# 06-SIM800C.net
KiCad netlist of a schematic drawn in Altium Designer
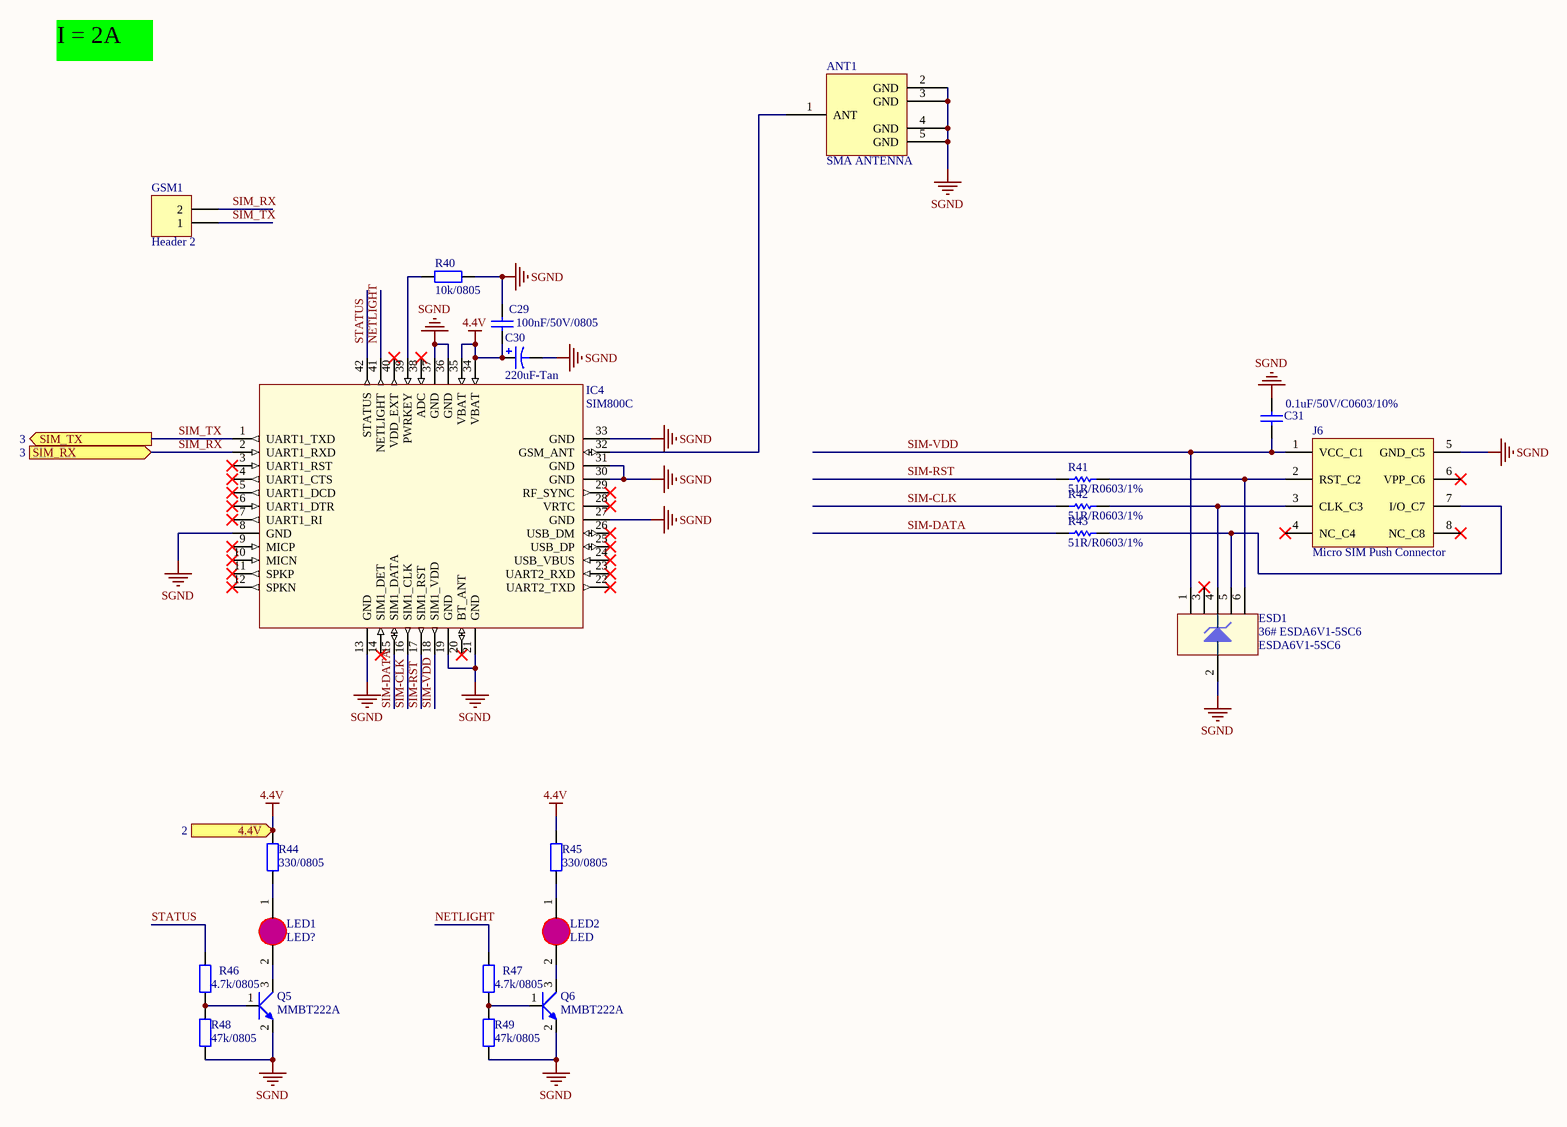
[diagram p0: 06-SIM800C.SchDoc]

(export (version "E")
  (design (tool "Eeschema 10.0.6"))
  (components
    (comp (ref "ANT1")
      (value "SMA ANTENNA")
      (footprint "atenna_ra")
      (libsource (lib "Air_System_lib") (part "SMA ANTENNA"))
    )
    (comp (ref "C29")
      (value "100nF/50V/0805")
      (footprint "Cap Ceramic 0805 SMD")
      (fields (field (name "PUBLISHER") "Altium Limited"))
      (libsource (lib "NBBLib 14-03-2012") (part "CapSMD"))
    )
    (comp (ref "C30")
      (value "220uF-Tan")
      (footprint "CAP TANT CASE E SMD")
      (libsource (lib "Air_System_lib") (part "CAP1210-Tan"))
    )
    (comp (ref "C31")
      (value "0.1uF/50V/C0603/10%")
      (footprint "Cap Ceramic 0603 SMD")
      (description "CAP CER 0.1UF 50V 10% X7R 0603")
      (fields
        (field (name "MANUFACTURER") "Murata Electronics North America")
        (field (name "MANUFACTURER PART NUMBER") "GRM188R71H104KA93D")
      )
      (libsource (lib "GSHT_181013") (part "0.1uF/50V/C0603/10%"))
    )
    (comp (ref "ESD1")
      (value "36# ESDA6V1-5SC6")
      (footprint "36# ESDA6V1-5SC6")
      (description "TRANSIL™ ARRAY FOR ESD PROTECTION")
      (fields (field (name "SUPPLIER PART NUMBER 1") "ESDA6V1-5SC6"))
      (libsource (lib "GSHT_181013") (part "36# ESDA6V1-5SC6"))
    )
    (comp (ref "GSM1")
      (value "Header 2")
      (footprint "Header_2")
      (description "Header, 2-Pin")
      (fields (field (name "PUBLISHER") "Altium Limited"))
      (libsource (lib "NBBLib 14-03-2012") (part "Header 2"))
    )
    (comp (ref "IC4")
      (value "SIM800C")
      (footprint "SIM800C")
      (description "SIM800C V1.00")
      (libsource (lib "LIEMTHANH_LIB") (part "SIM800C"))
    )
    (comp (ref "J6")
      (value "Micro SIM Push Connector")
      (footprint "9# SIM holder")
      (libsource (lib "GSHT_181013") (part "9#SIM Card Holder KF-016"))
    )
    (comp (ref "LED1")
      (value "LED?")
      (footprint "Led 0805R")
      (description "LED SMD 0805")
      (libsource (lib "NBBLib 14-03-2012") (part "LED0805"))
    )
    (comp (ref "LED2")
      (value "LED")
      (footprint "Led 0805R")
      (description "LED SMD 0805")
      (libsource (lib "NBBLib 14-03-2012") (part "LED0805"))
    )
    (comp (ref "Q5")
      (value "MMBT222A")
      (footprint "MMBT2222A")
      (libsource (lib "Air_System_lib") (part "MMBT222A"))
    )
    (comp (ref "Q6")
      (value "MMBT222A")
      (footprint "MMBT2222A")
      (libsource (lib "Air_System_lib") (part "MMBT222A"))
    )
    (comp (ref "R40")
      (value "10k/0805")
      (footprint "RESC2012(0805)")
      (description "Resistor SMD 0805")
      (fields (field (name "PUBLISHER") "Altium Limited"))
      (libsource (lib "") (part "R0805_1"))
    )
    (comp (ref "R41")
      (value "51R/R0603/1%")
      (footprint "Res 0603 SMD")
      (description "RES SMD 22 OHM 1% 1/10W 0603")
      (fields
        (field (name "MANUFACTURER") "Yageo")
        (field (name "MANUFACTURER PART NUMBER") "RC0603FR-0722RL")
      )
      (libsource (lib "GSHT_181013") (part "22R/R0603/1%"))
    )
    (comp (ref "R42")
      (value "51R/R0603/1%")
      (footprint "Res 0603 SMD")
      (description "RES SMD 22 OHM 1% 1/10W 0603")
      (fields
        (field (name "MANUFACTURER") "Yageo")
        (field (name "MANUFACTURER PART NUMBER") "RC0603FR-0722RL")
      )
      (libsource (lib "GSHT_181013") (part "22R/R0603/1%"))
    )
    (comp (ref "R43")
      (value "51R/R0603/1%")
      (footprint "Res 0603 SMD")
      (description "RES SMD 22 OHM 1% 1/10W 0603")
      (fields
        (field (name "MANUFACTURER") "Yageo")
        (field (name "MANUFACTURER PART NUMBER") "RC0603FR-0722RL")
      )
      (libsource (lib "GSHT_181013") (part "22R/R0603/1%"))
    )
    (comp (ref "R44")
      (value "330/0805")
      (footprint "RESC2012(0805)")
      (description "Resistor SMD 0805")
      (fields (field (name "Comment") "R0805") (field (name "PUBLISHER") "Altium Limited"))
      (libsource (lib "NBBLib 14-03-2012") (part "R0805"))
    )
    (comp (ref "R45")
      (value "330/0805")
      (footprint "RESC2012(0805)")
      (description "Resistor SMD 0805")
      (fields (field (name "Comment") "R0805") (field (name "PUBLISHER") "Altium Limited"))
      (libsource (lib "NBBLib 14-03-2012") (part "R0805"))
    )
    (comp (ref "R46")
      (value "4.7k/0805")
      (footprint "RESC2012(0805)")
      (description "Resistor SMD 0805")
      (fields (field (name "Comment") "R0805") (field (name "PUBLISHER") "Altium Limited"))
      (libsource (lib "NBBLib 14-03-2012") (part "R0805"))
    )
    (comp (ref "R47")
      (value "4.7k/0805")
      (footprint "RESC2012(0805)")
      (description "Resistor SMD 0805")
      (fields (field (name "Comment") "R0805") (field (name "PUBLISHER") "Altium Limited"))
      (libsource (lib "NBBLib 14-03-2012") (part "R0805"))
    )
    (comp (ref "R48")
      (value "47k/0805")
      (footprint "RESC2012(0805)")
      (description "Resistor SMD 0805")
      (fields (field (name "Comment") "R0805") (field (name "PUBLISHER") "Altium Limited"))
      (libsource (lib "NBBLib 14-03-2012") (part "R0805"))
    )
    (comp (ref "R49")
      (value "47k/0805")
      (footprint "RESC2012(0805)")
      (description "Resistor SMD 0805")
      (fields (field (name "Comment") "R0805") (field (name "PUBLISHER") "Altium Limited"))
      (libsource (lib "NBBLib 14-03-2012") (part "R0805"))
    )
  )
  (nets
    (net (code "2") (name "/NETLIGHT") (class "Default")
      (node (ref "IC4") (pin "41") (pinfunction "NETLIGHT_41") (pintype "output"))
      (node (ref "R47") (pin "1") (pinfunction "1_1") (pintype "passive"))
    )
    (net (code "3") (name "/SIM-CLK") (class "Default")
      (node (ref "IC4") (pin "16") (pinfunction "SIM1_CLK_16") (pintype "output"))
      (node (ref "R42") (pin "1") (pinfunction "1_1") (pintype "passive"))
    )
    (net (code "4") (name "/SIM-DATA") (class "Default")
      (node (ref "IC4") (pin "15") (pinfunction "SIM1_DATA_15") (pintype "bidirectional"))
      (node (ref "R43") (pin "1") (pinfunction "1_1") (pintype "passive"))
    )
    (net (code "5") (name "/SIM-RST") (class "Default")
      (node (ref "IC4") (pin "17") (pinfunction "SIM1_RST_17") (pintype "output"))
      (node (ref "R41") (pin "1") (pinfunction "1_1") (pintype "passive"))
    )
    (net (code "6") (name "/SIM-VDD") (class "Default")
      (node (ref "C31") (pin "1") (pinfunction "1_1") (pintype "passive"))
      (node (ref "ESD1") (pin "1") (pinfunction "IO1_1") (pintype "passive"))
      (node (ref "IC4") (pin "18") (pinfunction "SIM1_VDD_18") (pintype "output"))
      (node (ref "J6") (pin "1") (pinfunction "VCC_C1_1") (pintype "passive"))
    )
    (net (code "7") (name "/SIM_RX") (class "Default")
      (node (ref "GSM1") (pin "2") (pinfunction "2_2") (pintype "passive"))
      (node (ref "IC4") (pin "2") (pinfunction "UART1_RXD_2") (pintype "input"))
    )
    (net (code "8") (name "/SIM_TX") (class "Default")
      (node (ref "GSM1") (pin "1") (pinfunction "1_1") (pintype "passive"))
      (node (ref "IC4") (pin "1") (pinfunction "UART1_TXD_1") (pintype "output"))
    )
    (net (code "9") (name "/STATUS") (class "Default")
      (node (ref "IC4") (pin "42") (pinfunction "STATUS_42") (pintype "output"))
      (node (ref "R46") (pin "1") (pinfunction "1_1") (pintype "passive"))
    )
    (net (code "10") (name "4.4V") (class "Default")
      (node (ref "C29") (pin "1") (pinfunction "1_1") (pintype "passive"))
      (node (ref "C30") (pin "1") (pinfunction "1_1") (pintype "passive"))
      (node (ref "IC4") (pin "34") (pinfunction "VBAT_34") (pintype "input"))
      (node (ref "IC4") (pin "35") (pinfunction "VBAT_35") (pintype "input"))
      (node (ref "R44") (pin "1") (pinfunction "1_1") (pintype "passive"))
      (node (ref "R45") (pin "1") (pinfunction "1_1") (pintype "passive"))
    )
    (net (code "11") (name "Net-(ANT1-ANT)") (class "Default")
      (node (ref "ANT1") (pin "1") (pinfunction "ANT_1") (pintype "passive"))
      (node (ref "IC4") (pin "32") (pinfunction "GSM_ANT_32") (pintype "bidirectional"))
    )
    (net (code "12") (name "Net-(ESD1-IO3)") (class "Default")
      (node (ref "ESD1") (pin "4") (pinfunction "IO3_4") (pintype "passive"))
      (node (ref "J6") (pin "3") (pinfunction "CLK_C3_3") (pintype "passive"))
      (node (ref "R42") (pin "2") (pinfunction "2_2") (pintype "passive"))
    )
    (net (code "13") (name "Net-(ESD1-IO4)") (class "Default")
      (node (ref "ESD1") (pin "5") (pinfunction "IO4_5") (pintype "passive"))
      (node (ref "J6") (pin "7") (pinfunction "I/O_C7_7") (pintype "passive"))
      (node (ref "R43") (pin "2") (pinfunction "2_2") (pintype "passive"))
    )
    (net (code "14") (name "Net-(ESD1-IO5)") (class "Default")
      (node (ref "ESD1") (pin "6") (pinfunction "IO5_6") (pintype "passive"))
      (node (ref "J6") (pin "2") (pinfunction "RST_C2_2") (pintype "passive"))
      (node (ref "R41") (pin "2") (pinfunction "2_2") (pintype "passive"))
    )
    (net (code "15") (name "Net-(IC4-PWRKEY)") (class "Default")
      (node (ref "IC4") (pin "39") (pinfunction "PWRKEY_39") (pintype "input"))
      (node (ref "R40") (pin "1") (pinfunction "1_1") (pintype "passive"))
    )
    (net (code "16") (name "Net-(LED1-A)") (class "Default")
      (node (ref "LED1") (pin "1") (pinfunction "A_1") (pintype "passive"))
      (node (ref "R44") (pin "2") (pinfunction "2_2") (pintype "passive"))
    )
    (net (code "17") (name "Net-(LED1-K)") (class "Default")
      (node (ref "LED1") (pin "2") (pinfunction "K_2") (pintype "passive"))
      (node (ref "Q5") (pin "3") (pinfunction "3_3") (pintype "passive"))
    )
    (net (code "18") (name "Net-(LED2-A)") (class "Default")
      (node (ref "LED2") (pin "1") (pinfunction "A_1") (pintype "passive"))
      (node (ref "R45") (pin "2") (pinfunction "2_2") (pintype "passive"))
    )
    (net (code "19") (name "Net-(LED2-K)") (class "Default")
      (node (ref "LED2") (pin "2") (pinfunction "K_2") (pintype "passive"))
      (node (ref "Q6") (pin "3") (pinfunction "3_3") (pintype "passive"))
    )
    (net (code "20") (name "Net-(Q5-Pad1)") (class "Default")
      (node (ref "Q5") (pin "1") (pinfunction "1_1") (pintype "passive"))
      (node (ref "R46") (pin "2") (pinfunction "2_2") (pintype "passive"))
      (node (ref "R48") (pin "1") (pinfunction "1_1") (pintype "passive"))
    )
    (net (code "21") (name "Net-(Q6-Pad1)") (class "Default")
      (node (ref "Q6") (pin "1") (pinfunction "1_1") (pintype "passive"))
      (node (ref "R47") (pin "2") (pinfunction "2_2") (pintype "passive"))
      (node (ref "R49") (pin "1") (pinfunction "1_1") (pintype "passive"))
    )
    (net (code "22") (name "SGND") (class "Default")
      (node (ref "ANT1") (pin "2") (pinfunction "GND_2") (pintype "passive"))
      (node (ref "ANT1") (pin "3") (pinfunction "GND_3") (pintype "passive"))
      (node (ref "ANT1") (pin "4") (pinfunction "GND_4") (pintype "passive"))
      (node (ref "ANT1") (pin "5") (pinfunction "GND_5") (pintype "passive"))
      (node (ref "C29") (pin "2") (pinfunction "2_2") (pintype "passive"))
      (node (ref "C30") (pin "2") (pinfunction "2_2") (pintype "passive"))
      (node (ref "C31") (pin "2") (pinfunction "2_2") (pintype "passive"))
      (node (ref "ESD1") (pin "2") (pinfunction "GND_2") (pintype "passive"))
      (node (ref "IC4") (pin "13") (pinfunction "GND_13") (pintype "power_in"))
      (node (ref "IC4") (pin "19") (pinfunction "GND_19") (pintype "power_in"))
      (node (ref "IC4") (pin "21") (pinfunction "GND_21") (pintype "power_in"))
      (node (ref "IC4") (pin "27") (pinfunction "GND_27") (pintype "power_in"))
      (node (ref "IC4") (pin "30") (pinfunction "GND_30") (pintype "power_in"))
      (node (ref "IC4") (pin "31") (pinfunction "GND_31") (pintype "power_in"))
      (node (ref "IC4") (pin "33") (pinfunction "GND_33") (pintype "power_in"))
      (node (ref "IC4") (pin "36") (pinfunction "GND_36") (pintype "power_in"))
      (node (ref "IC4") (pin "37") (pinfunction "GND_37") (pintype "power_in"))
      (node (ref "IC4") (pin "8") (pinfunction "GND_8") (pintype "power_in"))
      (node (ref "J6") (pin "5") (pinfunction "GND_C5_5") (pintype "passive"))
      (node (ref "Q5") (pin "2") (pinfunction "2_2") (pintype "passive"))
      (node (ref "Q6") (pin "2") (pinfunction "2_2") (pintype "passive"))
      (node (ref "R40") (pin "2") (pinfunction "2_2") (pintype "passive"))
      (node (ref "R48") (pin "2") (pinfunction "2_2") (pintype "passive"))
      (node (ref "R49") (pin "2") (pinfunction "2_2") (pintype "passive"))
    )
    (net (code "23") (name "unconnected-(ESD1-IO2-Pad3)") (class "Default")
      (node (ref "ESD1") (pin "3") (pinfunction "IO2_3") (pintype "passive+no_connect"))
    )
    (net (code "24") (name "unconnected-(IC4-ADC-Pad38)") (class "Default")
      (node (ref "IC4") (pin "38") (pinfunction "ADC_38") (pintype "input+no_connect"))
    )
    (net (code "25") (name "unconnected-(IC4-BT_ANT-Pad20)") (class "Default")
      (node (ref "IC4") (pin "20") (pinfunction "BT_ANT_20") (pintype "bidirectional+no_connect"))
    )
    (net (code "26") (name "unconnected-(IC4-MICN-Pad10)") (class "Default")
      (node (ref "IC4") (pin "10") (pinfunction "MICN_10") (pintype "input+no_connect"))
    )
    (net (code "27") (name "unconnected-(IC4-MICP-Pad9)") (class "Default")
      (node (ref "IC4") (pin "9") (pinfunction "MICP_9") (pintype "input+no_connect"))
    )
    (net (code "28") (name "unconnected-(IC4-RF_SYNC-Pad29)") (class "Default")
      (node (ref "IC4") (pin "29") (pinfunction "RF_SYNC_29") (pintype "output+no_connect"))
    )
    (net (code "29") (name "unconnected-(IC4-SIM1_DET-Pad14)") (class "Default")
      (node (ref "IC4") (pin "14") (pinfunction "SIM1_DET_14") (pintype "input+no_connect"))
    )
    (net (code "30") (name "unconnected-(IC4-SPKN-Pad12)") (class "Default")
      (node (ref "IC4") (pin "12") (pinfunction "SPKN_12") (pintype "output+no_connect"))
    )
    (net (code "31") (name "unconnected-(IC4-SPKP-Pad11)") (class "Default")
      (node (ref "IC4") (pin "11") (pinfunction "SPKP_11") (pintype "output+no_connect"))
    )
    (net (code "32") (name "unconnected-(IC4-UART1_CTS-Pad4)") (class "Default")
      (node (ref "IC4") (pin "4") (pinfunction "UART1_CTS_4") (pintype "output+no_connect"))
    )
    (net (code "33") (name "unconnected-(IC4-UART1_DCD-Pad5)") (class "Default")
      (node (ref "IC4") (pin "5") (pinfunction "UART1_DCD_5") (pintype "output+no_connect"))
    )
    (net (code "34") (name "unconnected-(IC4-UART1_DTR-Pad6)") (class "Default")
      (node (ref "IC4") (pin "6") (pinfunction "UART1_DTR_6") (pintype "input+no_connect"))
    )
    (net (code "35") (name "unconnected-(IC4-UART1_RI-Pad7)") (class "Default")
      (node (ref "IC4") (pin "7") (pinfunction "UART1_RI_7") (pintype "output+no_connect"))
    )
    (net (code "36") (name "unconnected-(IC4-UART1_RST-Pad3)") (class "Default")
      (node (ref "IC4") (pin "3") (pinfunction "UART1_RST_3") (pintype "input+no_connect"))
    )
    (net (code "37") (name "unconnected-(IC4-UART2_RXD-Pad23)") (class "Default")
      (node (ref "IC4") (pin "23") (pinfunction "UART2_RXD_23") (pintype "input+no_connect"))
    )
    (net (code "38") (name "unconnected-(IC4-UART2_TXD-Pad22)") (class "Default")
      (node (ref "IC4") (pin "22") (pinfunction "UART2_TXD_22") (pintype "output+no_connect"))
    )
    (net (code "39") (name "unconnected-(IC4-USB_DM-Pad26)") (class "Default")
      (node (ref "IC4") (pin "26") (pinfunction "USB_DM_26") (pintype "bidirectional+no_connect"))
    )
    (net (code "40") (name "unconnected-(IC4-USB_DP-Pad25)") (class "Default")
      (node (ref "IC4") (pin "25") (pinfunction "USB_DP_25") (pintype "bidirectional+no_connect"))
    )
    (net (code "41") (name "unconnected-(IC4-USB_VBUS-Pad24)") (class "Default")
      (node (ref "IC4") (pin "24") (pinfunction "USB_VBUS_24") (pintype "input+no_connect"))
    )
    (net (code "42") (name "unconnected-(IC4-VDD_EXT-Pad40)") (class "Default")
      (node (ref "IC4") (pin "40") (pinfunction "VDD_EXT_40") (pintype "output+no_connect"))
    )
    (net (code "43") (name "unconnected-(IC4-VRTC-Pad28)") (class "Default")
      (node (ref "IC4") (pin "28") (pinfunction "VRTC_28") (pintype "passive+no_connect"))
    )
    (net (code "44") (name "unconnected-(J6-NC_C4-Pad4)") (class "Default")
      (node (ref "J6") (pin "4") (pinfunction "NC_C4_4") (pintype "passive+no_connect"))
    )
    (net (code "45") (name "unconnected-(J6-NC_C8-Pad8)") (class "Default")
      (node (ref "J6") (pin "8") (pinfunction "NC_C8_8") (pintype "passive+no_connect"))
    )
    (net (code "46") (name "unconnected-(J6-VPP_C6-Pad6)") (class "Default")
      (node (ref "J6") (pin "6") (pinfunction "VPP_C6_6") (pintype "passive+no_connect"))
    )
  )
)
